# PhasedArrayReceiver.net
KiCad netlist of a schematic drawn in EAGLE
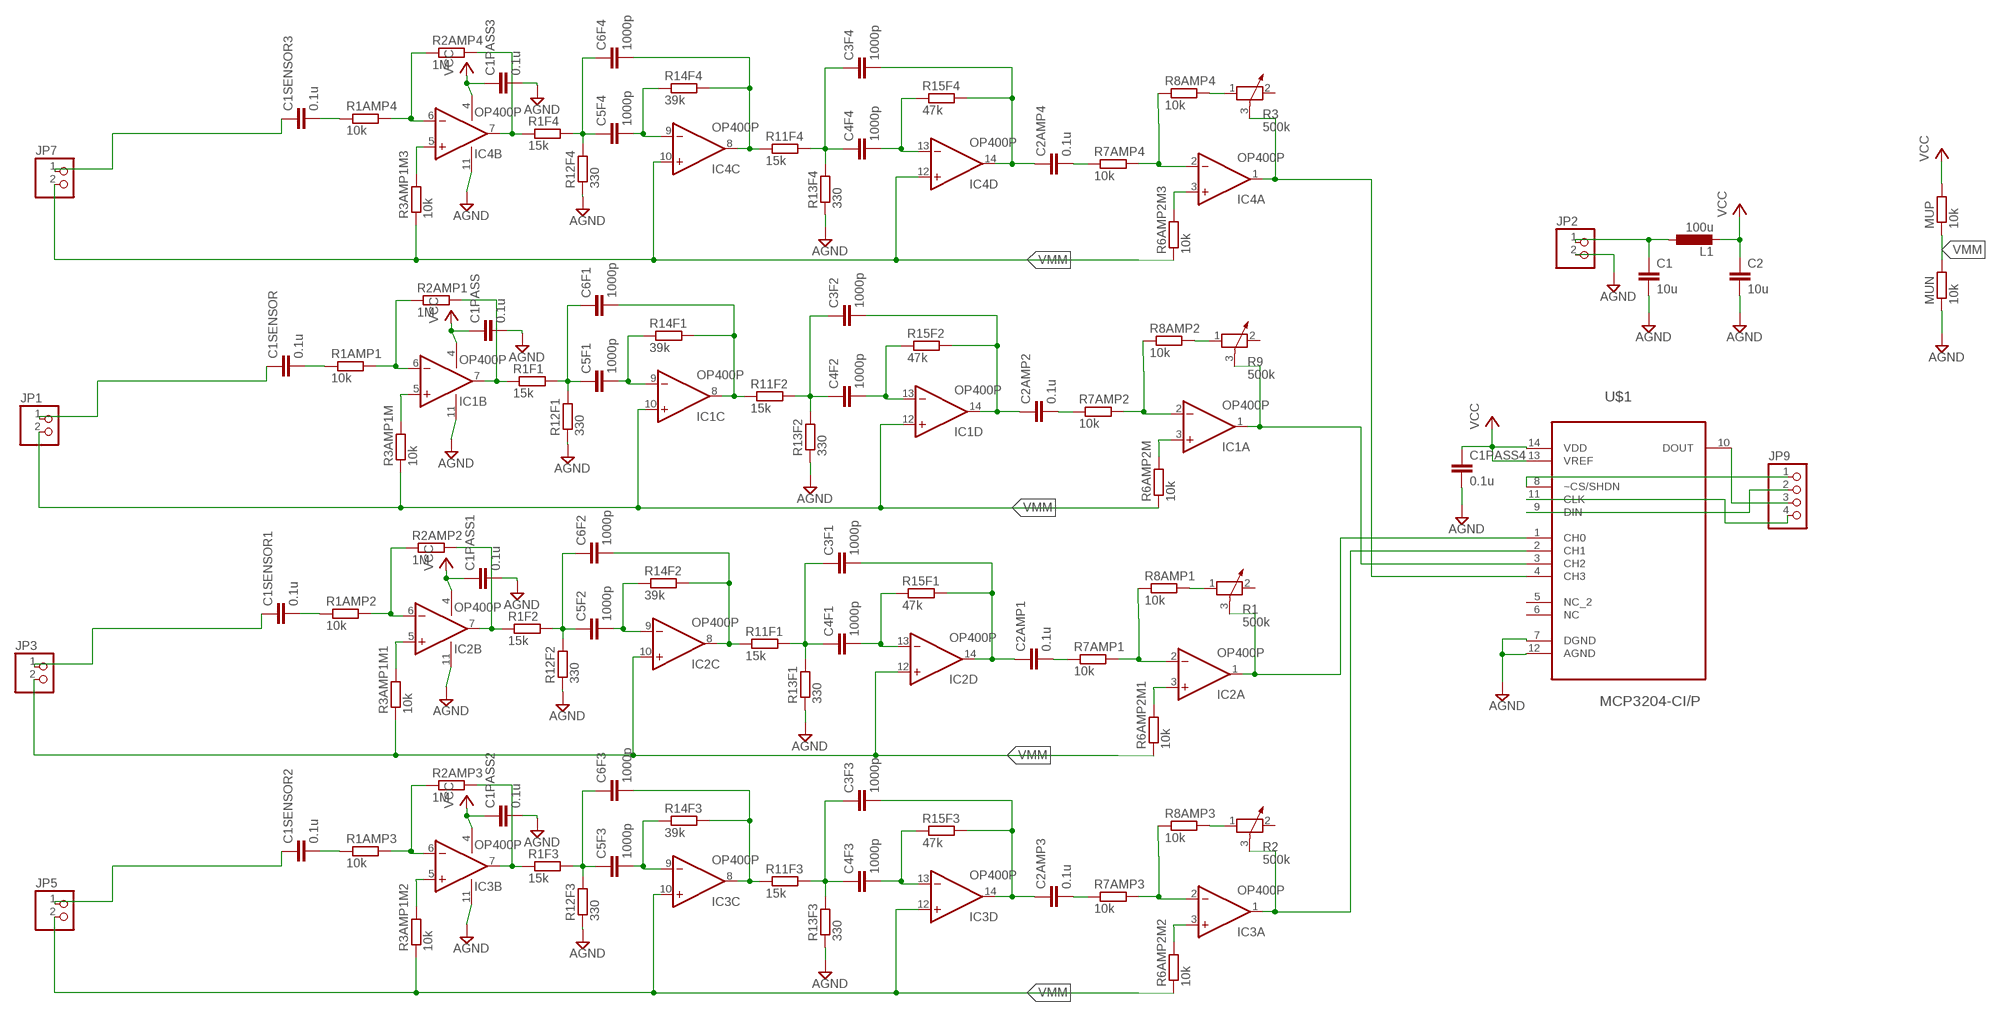
[diagram p0: schematic, sheet 1]

(export (version "E")
  (design (tool "Eeschema 10.0.6"))
  (components
    (comp (ref "C1")
      (value "10u")
      (footprint "eagle-import:C025-024X044")
      (libsource (lib "eagle-import") (part "C-EU025-024X044"))
    )
    (comp (ref "C1PASS")
      (value "0.1u")
      (footprint "eagle-import:C025-024X044")
      (libsource (lib "eagle-import") (part "C-EU025-024X044"))
    )
    (comp (ref "C1PASS1")
      (value "0.1u")
      (footprint "eagle-import:C025-024X044")
      (libsource (lib "eagle-import") (part "C-EU025-024X044"))
    )
    (comp (ref "C1PASS2")
      (value "0.1u")
      (footprint "eagle-import:C025-024X044")
      (libsource (lib "eagle-import") (part "C-EU025-024X044"))
    )
    (comp (ref "C1PASS3")
      (value "0.1u")
      (footprint "eagle-import:C025-024X044")
      (libsource (lib "eagle-import") (part "C-EU025-024X044"))
    )
    (comp (ref "C1PASS4")
      (value "0.1u")
      (footprint "eagle-import:C025-024X044")
      (libsource (lib "eagle-import") (part "C-EU025-024X044"))
    )
    (comp (ref "C1SENSOR")
      (value "0.1u")
      (footprint "eagle-import:C0603K")
      (libsource (lib "eagle-import") (part "C-EUC0603K"))
    )
    (comp (ref "C1SENSOR1")
      (value "0.1u")
      (footprint "eagle-import:C0603K")
      (libsource (lib "eagle-import") (part "C-EUC0603K"))
    )
    (comp (ref "C1SENSOR2")
      (value "0.1u")
      (footprint "eagle-import:C0603K")
      (libsource (lib "eagle-import") (part "C-EUC0603K"))
    )
    (comp (ref "C1SENSOR3")
      (value "0.1u")
      (footprint "eagle-import:C0603K")
      (libsource (lib "eagle-import") (part "C-EUC0603K"))
    )
    (comp (ref "C2")
      (value "10u")
      (footprint "eagle-import:C025-024X044")
      (libsource (lib "eagle-import") (part "C-EU025-024X044"))
    )
    (comp (ref "C2AMP1")
      (value "0.1u")
      (footprint "eagle-import:C0603K")
      (libsource (lib "eagle-import") (part "C-EUC0603K"))
    )
    (comp (ref "C2AMP2")
      (value "0.1u")
      (footprint "eagle-import:C0603K")
      (libsource (lib "eagle-import") (part "C-EUC0603K"))
    )
    (comp (ref "C2AMP3")
      (value "0.1u")
      (footprint "eagle-import:C0603K")
      (libsource (lib "eagle-import") (part "C-EUC0603K"))
    )
    (comp (ref "C2AMP4")
      (value "0.1u")
      (footprint "eagle-import:C0603K")
      (libsource (lib "eagle-import") (part "C-EUC0603K"))
    )
    (comp (ref "C3F1")
      (value "1000p")
      (footprint "eagle-import:C0603K")
      (libsource (lib "eagle-import") (part "C-EUC0603K"))
    )
    (comp (ref "C3F2")
      (value "1000p")
      (footprint "eagle-import:C0603K")
      (libsource (lib "eagle-import") (part "C-EUC0603K"))
    )
    (comp (ref "C3F3")
      (value "1000p")
      (footprint "eagle-import:C0603K")
      (libsource (lib "eagle-import") (part "C-EUC0603K"))
    )
    (comp (ref "C3F4")
      (value "1000p")
      (footprint "eagle-import:C0603K")
      (libsource (lib "eagle-import") (part "C-EUC0603K"))
    )
    (comp (ref "C4F1")
      (value "1000p")
      (footprint "eagle-import:C0603K")
      (libsource (lib "eagle-import") (part "C-EUC0603K"))
    )
    (comp (ref "C4F2")
      (value "1000p")
      (footprint "eagle-import:C0603K")
      (libsource (lib "eagle-import") (part "C-EUC0603K"))
    )
    (comp (ref "C4F3")
      (value "1000p")
      (footprint "eagle-import:C0603K")
      (libsource (lib "eagle-import") (part "C-EUC0603K"))
    )
    (comp (ref "C4F4")
      (value "1000p")
      (footprint "eagle-import:C0603K")
      (libsource (lib "eagle-import") (part "C-EUC0603K"))
    )
    (comp (ref "C5F1")
      (value "1000p")
      (footprint "eagle-import:C0603K")
      (libsource (lib "eagle-import") (part "C-EUC0603K"))
    )
    (comp (ref "C5F2")
      (value "1000p")
      (footprint "eagle-import:C0603K")
      (libsource (lib "eagle-import") (part "C-EUC0603K"))
    )
    (comp (ref "C5F3")
      (value "1000p")
      (footprint "eagle-import:C0603K")
      (libsource (lib "eagle-import") (part "C-EUC0603K"))
    )
    (comp (ref "C5F4")
      (value "1000p")
      (footprint "eagle-import:C0603K")
      (libsource (lib "eagle-import") (part "C-EUC0603K"))
    )
    (comp (ref "C6F1")
      (value "1000p")
      (footprint "eagle-import:C0603K")
      (libsource (lib "eagle-import") (part "C-EUC0603K"))
    )
    (comp (ref "C6F2")
      (value "1000p")
      (footprint "eagle-import:C0603K")
      (libsource (lib "eagle-import") (part "C-EUC0603K"))
    )
    (comp (ref "C6F3")
      (value "1000p")
      (footprint "eagle-import:C0603K")
      (libsource (lib "eagle-import") (part "C-EUC0603K"))
    )
    (comp (ref "C6F4")
      (value "1000p")
      (footprint "eagle-import:C0603K")
      (libsource (lib "eagle-import") (part "C-EUC0603K"))
    )
    (comp (ref "IC1")
      (value "OP400P")
      (footprint "eagle-import:DIL14")
      (libsource (lib "eagle-import") (part "OP400P"))
    )
    (comp (ref "IC2")
      (value "OP400P")
      (footprint "eagle-import:DIL14")
      (libsource (lib "eagle-import") (part "OP400P"))
    )
    (comp (ref "IC3")
      (value "OP400P")
      (footprint "eagle-import:DIL14")
      (libsource (lib "eagle-import") (part "OP400P"))
    )
    (comp (ref "IC4")
      (value "OP400P")
      (footprint "eagle-import:DIL14")
      (libsource (lib "eagle-import") (part "OP400P"))
    )
    (comp (ref "JP1")
      (value "PINHD-1X2")
      (footprint "eagle-import:1X02")
      (libsource (lib "eagle-import") (part "PINHD-1X2"))
    )
    (comp (ref "JP2")
      (value "PINHD-1X2")
      (footprint "eagle-import:1X02")
      (libsource (lib "eagle-import") (part "PINHD-1X2"))
    )
    (comp (ref "JP3")
      (value "PINHD-1X2")
      (footprint "eagle-import:1X02")
      (libsource (lib "eagle-import") (part "PINHD-1X2"))
    )
    (comp (ref "JP5")
      (value "PINHD-1X2")
      (footprint "eagle-import:1X02")
      (libsource (lib "eagle-import") (part "PINHD-1X2"))
    )
    (comp (ref "JP7")
      (value "PINHD-1X2")
      (footprint "eagle-import:1X02")
      (libsource (lib "eagle-import") (part "PINHD-1X2"))
    )
    (comp (ref "JP9")
      (value "PINHD-1X4")
      (footprint "eagle-import:1X04")
      (libsource (lib "eagle-import") (part "PINHD-1X4"))
    )
    (comp (ref "L1")
      (value "100u")
      (footprint "eagle-import:0207_7")
      (libsource (lib "eagle-import") (part "L-EU0207/7"))
    )
    (comp (ref "MUN")
      (value "10k")
      (footprint "eagle-import:0207_7")
      (libsource (lib "eagle-import") (part "R-EU_0207/7"))
    )
    (comp (ref "MUP")
      (value "10k")
      (footprint "eagle-import:0207_7")
      (libsource (lib "eagle-import") (part "R-EU_0207/7"))
    )
    (comp (ref "R1")
      (value "500k")
      (footprint "eagle-import:PT-10")
      (libsource (lib "eagle-import") (part "POTENTIOMETER_PT-10"))
    )
    (comp (ref "R1AMP1")
      (value "10k")
      (footprint "eagle-import:R0603")
      (libsource (lib "eagle-import") (part "R-EU_R0603"))
    )
    (comp (ref "R1AMP2")
      (value "10k")
      (footprint "eagle-import:R0603")
      (libsource (lib "eagle-import") (part "R-EU_R0603"))
    )
    (comp (ref "R1AMP3")
      (value "10k")
      (footprint "eagle-import:R0603")
      (libsource (lib "eagle-import") (part "R-EU_R0603"))
    )
    (comp (ref "R1AMP4")
      (value "10k")
      (footprint "eagle-import:R0603")
      (libsource (lib "eagle-import") (part "R-EU_R0603"))
    )
    (comp (ref "R1F1")
      (value "15k")
      (footprint "eagle-import:0207_7")
      (libsource (lib "eagle-import") (part "R-EU_0207/7"))
    )
    (comp (ref "R1F2")
      (value "15k")
      (footprint "eagle-import:0207_7")
      (libsource (lib "eagle-import") (part "R-EU_0207/7"))
    )
    (comp (ref "R1F3")
      (value "15k")
      (footprint "eagle-import:0207_7")
      (libsource (lib "eagle-import") (part "R-EU_0207/7"))
    )
    (comp (ref "R1F4")
      (value "15k")
      (footprint "eagle-import:0207_7")
      (libsource (lib "eagle-import") (part "R-EU_0207/7"))
    )
    (comp (ref "R2")
      (value "500k")
      (footprint "eagle-import:PT-10")
      (libsource (lib "eagle-import") (part "POTENTIOMETER_PT-10"))
    )
    (comp (ref "R2AMP1")
      (value "1M")
      (footprint "eagle-import:R0603")
      (libsource (lib "eagle-import") (part "R-EU_R0603"))
    )
    (comp (ref "R2AMP2")
      (value "1M")
      (footprint "eagle-import:R0603")
      (libsource (lib "eagle-import") (part "R-EU_R0603"))
    )
    (comp (ref "R2AMP3")
      (value "1M")
      (footprint "eagle-import:R0603")
      (libsource (lib "eagle-import") (part "R-EU_R0603"))
    )
    (comp (ref "R2AMP4")
      (value "1M")
      (footprint "eagle-import:R0603")
      (libsource (lib "eagle-import") (part "R-EU_R0603"))
    )
    (comp (ref "R3")
      (value "500k")
      (footprint "eagle-import:PT-10")
      (libsource (lib "eagle-import") (part "POTENTIOMETER_PT-10"))
    )
    (comp (ref "R3AMP1M")
      (value "10k")
      (footprint "eagle-import:R0603")
      (libsource (lib "eagle-import") (part "R-EU_R0603"))
    )
    (comp (ref "R3AMP1M1")
      (value "10k")
      (footprint "eagle-import:R0603")
      (libsource (lib "eagle-import") (part "R-EU_R0603"))
    )
    (comp (ref "R3AMP1M2")
      (value "10k")
      (footprint "eagle-import:R0603")
      (libsource (lib "eagle-import") (part "R-EU_R0603"))
    )
    (comp (ref "R3AMP1M3")
      (value "10k")
      (footprint "eagle-import:R0603")
      (libsource (lib "eagle-import") (part "R-EU_R0603"))
    )
    (comp (ref "R6AMP2M")
      (value "10k")
      (footprint "eagle-import:R0603")
      (libsource (lib "eagle-import") (part "R-EU_R0603"))
    )
    (comp (ref "R6AMP2M1")
      (value "10k")
      (footprint "eagle-import:R0603")
      (libsource (lib "eagle-import") (part "R-EU_R0603"))
    )
    (comp (ref "R6AMP2M2")
      (value "10k")
      (footprint "eagle-import:R0603")
      (libsource (lib "eagle-import") (part "R-EU_R0603"))
    )
    (comp (ref "R6AMP2M3")
      (value "10k")
      (footprint "eagle-import:R0603")
      (libsource (lib "eagle-import") (part "R-EU_R0603"))
    )
    (comp (ref "R7AMP1")
      (value "10k")
      (footprint "eagle-import:R0603")
      (libsource (lib "eagle-import") (part "R-EU_R0603"))
    )
    (comp (ref "R7AMP2")
      (value "10k")
      (footprint "eagle-import:R0603")
      (libsource (lib "eagle-import") (part "R-EU_R0603"))
    )
    (comp (ref "R7AMP3")
      (value "10k")
      (footprint "eagle-import:R0603")
      (libsource (lib "eagle-import") (part "R-EU_R0603"))
    )
    (comp (ref "R7AMP4")
      (value "10k")
      (footprint "eagle-import:R0603")
      (libsource (lib "eagle-import") (part "R-EU_R0603"))
    )
    (comp (ref "R8AMP1")
      (value "10k")
      (footprint "eagle-import:R0603")
      (libsource (lib "eagle-import") (part "R-EU_R0603"))
    )
    (comp (ref "R8AMP2")
      (value "10k")
      (footprint "eagle-import:R0603")
      (libsource (lib "eagle-import") (part "R-EU_R0603"))
    )
    (comp (ref "R8AMP3")
      (value "10k")
      (footprint "eagle-import:R0603")
      (libsource (lib "eagle-import") (part "R-EU_R0603"))
    )
    (comp (ref "R8AMP4")
      (value "10k")
      (footprint "eagle-import:R0603")
      (libsource (lib "eagle-import") (part "R-EU_R0603"))
    )
    (comp (ref "R9")
      (value "500k")
      (footprint "eagle-import:PT-10")
      (libsource (lib "eagle-import") (part "POTENTIOMETER_PT-10"))
    )
    (comp (ref "R11F1")
      (value "15k")
      (footprint "eagle-import:R0603")
      (libsource (lib "eagle-import") (part "R-EU_R0603"))
    )
    (comp (ref "R11F2")
      (value "15k")
      (footprint "eagle-import:R0603")
      (libsource (lib "eagle-import") (part "R-EU_R0603"))
    )
    (comp (ref "R11F3")
      (value "15k")
      (footprint "eagle-import:R0603")
      (libsource (lib "eagle-import") (part "R-EU_R0603"))
    )
    (comp (ref "R11F4")
      (value "15k")
      (footprint "eagle-import:R0603")
      (libsource (lib "eagle-import") (part "R-EU_R0603"))
    )
    (comp (ref "R12F1")
      (value "330")
      (footprint "eagle-import:R0603")
      (libsource (lib "eagle-import") (part "R-EU_R0603"))
    )
    (comp (ref "R12F2")
      (value "330")
      (footprint "eagle-import:R0603")
      (libsource (lib "eagle-import") (part "R-EU_R0603"))
    )
    (comp (ref "R12F3")
      (value "330")
      (footprint "eagle-import:R0603")
      (libsource (lib "eagle-import") (part "R-EU_R0603"))
    )
    (comp (ref "R12F4")
      (value "330")
      (footprint "eagle-import:R0603")
      (libsource (lib "eagle-import") (part "R-EU_R0603"))
    )
    (comp (ref "R13F1")
      (value "330")
      (footprint "eagle-import:R0603")
      (libsource (lib "eagle-import") (part "R-EU_R0603"))
    )
    (comp (ref "R13F2")
      (value "330")
      (footprint "eagle-import:R0603")
      (libsource (lib "eagle-import") (part "R-EU_R0603"))
    )
    (comp (ref "R13F3")
      (value "330")
      (footprint "eagle-import:R0603")
      (libsource (lib "eagle-import") (part "R-EU_R0603"))
    )
    (comp (ref "R13F4")
      (value "330")
      (footprint "eagle-import:R0603")
      (libsource (lib "eagle-import") (part "R-EU_R0603"))
    )
    (comp (ref "R14F1")
      (value "39k")
      (footprint "eagle-import:0207_7")
      (libsource (lib "eagle-import") (part "R-EU_0207/7"))
    )
    (comp (ref "R14F2")
      (value "39k")
      (footprint "eagle-import:0207_7")
      (libsource (lib "eagle-import") (part "R-EU_0207/7"))
    )
    (comp (ref "R14F3")
      (value "39k")
      (footprint "eagle-import:0207_7")
      (libsource (lib "eagle-import") (part "R-EU_0207/7"))
    )
    (comp (ref "R14F4")
      (value "39k")
      (footprint "eagle-import:0207_7")
      (libsource (lib "eagle-import") (part "R-EU_0207/7"))
    )
    (comp (ref "R15F1")
      (value "47k")
      (footprint "eagle-import:0207_7")
      (libsource (lib "eagle-import") (part "R-EU_0207/7"))
    )
    (comp (ref "R15F2")
      (value "47k")
      (footprint "eagle-import:0207_7")
      (libsource (lib "eagle-import") (part "R-EU_0207/7"))
    )
    (comp (ref "R15F3")
      (value "47k")
      (footprint "eagle-import:0207_7")
      (libsource (lib "eagle-import") (part "R-EU_0207/7"))
    )
    (comp (ref "R15F4")
      (value "47k")
      (footprint "eagle-import:0207_7")
      (libsource (lib "eagle-import") (part "R-EU_0207/7"))
    )
    (comp (ref "U$1")
      (value "MCP3204-CI/P")
      (footprint "eagle-import:DIP254P762X432-14")
      (fields (field (name "MF") "Microchip"))
      (libsource (lib "eagle-import") (part "MCP3204-CI/P"))
    )
  )
  (nets
    (net (code "1") (name "AGND") (class "Default")
      (node (ref "C1") (pin "2") (pinfunction "2_2") (pintype "passive"))
      (node (ref "C1PASS") (pin "2") (pinfunction "2_2") (pintype "passive"))
      (node (ref "C1PASS1") (pin "2") (pinfunction "2_2") (pintype "passive"))
      (node (ref "C1PASS2") (pin "2") (pinfunction "2_2") (pintype "passive"))
      (node (ref "C1PASS3") (pin "2") (pinfunction "2_2") (pintype "passive"))
      (node (ref "C1PASS4") (pin "2") (pinfunction "2_2") (pintype "passive"))
      (node (ref "C2") (pin "2") (pinfunction "2_2") (pintype "passive"))
      (node (ref "IC1") (pin "11") (pinfunction "V-_11") (pintype "power_in"))
      (node (ref "IC2") (pin "11") (pinfunction "V-_11") (pintype "power_in"))
      (node (ref "IC3") (pin "11") (pinfunction "V-_11") (pintype "power_in"))
      (node (ref "IC4") (pin "11") (pinfunction "V-_11") (pintype "power_in"))
      (node (ref "JP2") (pin "2") (pinfunction "2_2") (pintype "passive"))
      (node (ref "MUN") (pin "1") (pinfunction "1_1") (pintype "passive"))
      (node (ref "R12F1") (pin "1") (pinfunction "1_1") (pintype "passive"))
      (node (ref "R12F2") (pin "1") (pinfunction "1_1") (pintype "passive"))
      (node (ref "R12F3") (pin "1") (pinfunction "1_1") (pintype "passive"))
      (node (ref "R12F4") (pin "1") (pinfunction "1_1") (pintype "passive"))
      (node (ref "R13F1") (pin "1") (pinfunction "1_1") (pintype "passive"))
      (node (ref "R13F2") (pin "1") (pinfunction "1_1") (pintype "passive"))
      (node (ref "R13F3") (pin "1") (pinfunction "1_1") (pintype "passive"))
      (node (ref "R13F4") (pin "1") (pinfunction "1_1") (pintype "passive"))
      (node (ref "U$1") (pin "12") (pinfunction "AGND_12") (pintype "passive"))
      (node (ref "U$1") (pin "7") (pinfunction "DGND_7") (pintype "passive"))
    )
    (net (code "2") (name "Net-(C1-Pad1)") (class "Default")
      (node (ref "C1") (pin "1") (pinfunction "1_1") (pintype "passive"))
      (node (ref "JP2") (pin "1") (pinfunction "1_1") (pintype "passive"))
      (node (ref "L1") (pin "1") (pinfunction "1_1") (pintype "passive"))
    )
    (net (code "3") (name "Net-(C1SENSOR-Pad1)") (class "Default")
      (node (ref "C1SENSOR") (pin "1") (pinfunction "1_1") (pintype "passive"))
      (node (ref "JP1") (pin "1") (pinfunction "1_1") (pintype "passive"))
    )
    (net (code "4") (name "Net-(C1SENSOR-Pad2)") (class "Default")
      (node (ref "C1SENSOR") (pin "2") (pinfunction "2_2") (pintype "passive"))
      (node (ref "R1AMP1") (pin "1") (pinfunction "1_1") (pintype "passive"))
    )
    (net (code "5") (name "Net-(C1SENSOR1-Pad1)") (class "Default")
      (node (ref "C1SENSOR1") (pin "1") (pinfunction "1_1") (pintype "passive"))
      (node (ref "JP3") (pin "1") (pinfunction "1_1") (pintype "passive"))
    )
    (net (code "6") (name "Net-(C1SENSOR1-Pad2)") (class "Default")
      (node (ref "C1SENSOR1") (pin "2") (pinfunction "2_2") (pintype "passive"))
      (node (ref "R1AMP2") (pin "1") (pinfunction "1_1") (pintype "passive"))
    )
    (net (code "7") (name "Net-(C1SENSOR2-Pad1)") (class "Default")
      (node (ref "C1SENSOR2") (pin "1") (pinfunction "1_1") (pintype "passive"))
      (node (ref "JP5") (pin "1") (pinfunction "1_1") (pintype "passive"))
    )
    (net (code "8") (name "Net-(C1SENSOR2-Pad2)") (class "Default")
      (node (ref "C1SENSOR2") (pin "2") (pinfunction "2_2") (pintype "passive"))
      (node (ref "R1AMP3") (pin "1") (pinfunction "1_1") (pintype "passive"))
    )
    (net (code "9") (name "Net-(C1SENSOR3-Pad1)") (class "Default")
      (node (ref "C1SENSOR3") (pin "1") (pinfunction "1_1") (pintype "passive"))
      (node (ref "JP7") (pin "1") (pinfunction "1_1") (pintype "passive"))
    )
    (net (code "10") (name "Net-(C1SENSOR3-Pad2)") (class "Default")
      (node (ref "C1SENSOR3") (pin "2") (pinfunction "2_2") (pintype "passive"))
      (node (ref "R1AMP4") (pin "1") (pinfunction "1_1") (pintype "passive"))
    )
    (net (code "11") (name "Net-(C2AMP1-Pad2)") (class "Default")
      (node (ref "C2AMP1") (pin "2") (pinfunction "2_2") (pintype "passive"))
      (node (ref "R7AMP1") (pin "1") (pinfunction "1_1") (pintype "passive"))
    )
    (net (code "12") (name "Net-(C2AMP2-Pad2)") (class "Default")
      (node (ref "C2AMP2") (pin "2") (pinfunction "2_2") (pintype "passive"))
      (node (ref "R7AMP2") (pin "1") (pinfunction "1_1") (pintype "passive"))
    )
    (net (code "13") (name "Net-(C2AMP3-Pad2)") (class "Default")
      (node (ref "C2AMP3") (pin "2") (pinfunction "2_2") (pintype "passive"))
      (node (ref "R7AMP3") (pin "1") (pinfunction "1_1") (pintype "passive"))
    )
    (net (code "14") (name "Net-(C2AMP4-Pad2)") (class "Default")
      (node (ref "C2AMP4") (pin "2") (pinfunction "2_2") (pintype "passive"))
      (node (ref "R7AMP4") (pin "1") (pinfunction "1_1") (pintype "passive"))
    )
    (net (code "15") (name "Net-(C3F1-Pad1)") (class "Default")
      (node (ref "C3F1") (pin "1") (pinfunction "1_1") (pintype "passive"))
      (node (ref "C4F1") (pin "1") (pinfunction "1_1") (pintype "passive"))
      (node (ref "R11F1") (pin "2") (pinfunction "2_2") (pintype "passive"))
      (node (ref "R13F1") (pin "2") (pinfunction "2_2") (pintype "passive"))
    )
    (net (code "16") (name "Net-(C3F2-Pad1)") (class "Default")
      (node (ref "C3F2") (pin "1") (pinfunction "1_1") (pintype "passive"))
      (node (ref "C4F2") (pin "1") (pinfunction "1_1") (pintype "passive"))
      (node (ref "R11F2") (pin "2") (pinfunction "2_2") (pintype "passive"))
      (node (ref "R13F2") (pin "2") (pinfunction "2_2") (pintype "passive"))
    )
    (net (code "17") (name "Net-(C3F3-Pad1)") (class "Default")
      (node (ref "C3F3") (pin "1") (pinfunction "1_1") (pintype "passive"))
      (node (ref "C4F3") (pin "1") (pinfunction "1_1") (pintype "passive"))
      (node (ref "R11F3") (pin "2") (pinfunction "2_2") (pintype "passive"))
      (node (ref "R13F3") (pin "2") (pinfunction "2_2") (pintype "passive"))
    )
    (net (code "18") (name "Net-(C3F4-Pad1)") (class "Default")
      (node (ref "C3F4") (pin "1") (pinfunction "1_1") (pintype "passive"))
      (node (ref "C4F4") (pin "1") (pinfunction "1_1") (pintype "passive"))
      (node (ref "R11F4") (pin "2") (pinfunction "2_2") (pintype "passive"))
      (node (ref "R13F4") (pin "2") (pinfunction "2_2") (pintype "passive"))
    )
    (net (code "19") (name "Net-(C5F1-Pad1)") (class "Default")
      (node (ref "C5F1") (pin "1") (pinfunction "1_1") (pintype "passive"))
      (node (ref "C6F1") (pin "1") (pinfunction "1_1") (pintype "passive"))
      (node (ref "R12F1") (pin "2") (pinfunction "2_2") (pintype "passive"))
      (node (ref "R1F1") (pin "2") (pinfunction "2_2") (pintype "passive"))
    )
    (net (code "20") (name "Net-(C5F2-Pad1)") (class "Default")
      (node (ref "C5F2") (pin "1") (pinfunction "1_1") (pintype "passive"))
      (node (ref "C6F2") (pin "1") (pinfunction "1_1") (pintype "passive"))
      (node (ref "R12F2") (pin "2") (pinfunction "2_2") (pintype "passive"))
      (node (ref "R1F2") (pin "2") (pinfunction "2_2") (pintype "passive"))
    )
    (net (code "21") (name "Net-(C5F3-Pad1)") (class "Default")
      (node (ref "C5F3") (pin "1") (pinfunction "1_1") (pintype "passive"))
      (node (ref "C6F3") (pin "1") (pinfunction "1_1") (pintype "passive"))
      (node (ref "R12F3") (pin "2") (pinfunction "2_2") (pintype "passive"))
      (node (ref "R1F3") (pin "2") (pinfunction "2_2") (pintype "passive"))
    )
    (net (code "22") (name "Net-(C5F4-Pad1)") (class "Default")
      (node (ref "C5F4") (pin "1") (pinfunction "1_1") (pintype "passive"))
      (node (ref "C6F4") (pin "1") (pinfunction "1_1") (pintype "passive"))
      (node (ref "R12F4") (pin "2") (pinfunction "2_2") (pintype "passive"))
      (node (ref "R1F4") (pin "2") (pinfunction "2_2") (pintype "passive"))
    )
    (net (code "23") (name "Net-(IC1A-+IN)") (class "Default")
      (node (ref "IC1") (pin "3") (pinfunction "+IN_3") (pintype "input"))
      (node (ref "R6AMP2M") (pin "2") (pinfunction "2_2") (pintype "passive"))
    )
    (net (code "24") (name "Net-(IC1A--IN)") (class "Default")
      (node (ref "IC1") (pin "2") (pinfunction "-IN_2") (pintype "input"))
      (node (ref "R7AMP2") (pin "2") (pinfunction "2_2") (pintype "passive"))
      (node (ref "R8AMP2") (pin "1") (pinfunction "1_1") (pintype "passive"))
    )
    (net (code "25") (name "Net-(IC1A-OUT)") (class "Default")
      (node (ref "IC1") (pin "1") (pinfunction "OUT_1") (pintype "output"))
      (node (ref "R9") (pin "3") (pinfunction "3_3") (pintype "passive"))
      (node (ref "U$1") (pin "3") (pinfunction "CH2_3") (pintype "input"))
    )
    (net (code "26") (name "Net-(IC1B-+IN)") (class "Default")
      (node (ref "IC1") (pin "5") (pinfunction "+IN_5") (pintype "input"))
      (node (ref "R3AMP1M") (pin "2") (pinfunction "2_2") (pintype "passive"))
    )
    (net (code "27") (name "Net-(IC1B--IN)") (class "Default")
      (node (ref "IC1") (pin "6") (pinfunction "-IN_6") (pintype "input"))
      (node (ref "R1AMP1") (pin "2") (pinfunction "2_2") (pintype "passive"))
      (node (ref "R2AMP1") (pin "1") (pinfunction "1_1") (pintype "passive"))
    )
    (net (code "28") (name "Net-(IC1B-OUT)") (class "Default")
      (node (ref "IC1") (pin "7") (pinfunction "OUT_7") (pintype "output"))
      (node (ref "R1F1") (pin "1") (pinfunction "1_1") (pintype "passive"))
      (node (ref "R2AMP1") (pin "2") (pinfunction "2_2") (pintype "passive"))
    )
    (net (code "29") (name "Net-(IC1C--IN)") (class "Default")
      (node (ref "C5F1") (pin "2") (pinfunction "2_2") (pintype "passive"))
      (node (ref "IC1") (pin "9") (pinfunction "-IN_9") (pintype "input"))
      (node (ref "R14F1") (pin "1") (pinfunction "1_1") (pintype "passive"))
    )
    (net (code "30") (name "Net-(IC1C-OUT)") (class "Default")
      (node (ref "C6F1") (pin "2") (pinfunction "2_2") (pintype "passive"))
      (node (ref "IC1") (pin "8") (pinfunction "OUT_8") (pintype "output"))
      (node (ref "R11F2") (pin "1") (pinfunction "1_1") (pintype "passive"))
      (node (ref "R14F1") (pin "2") (pinfunction "2_2") (pintype "passive"))
    )
    (net (code "31") (name "Net-(IC1D--IN)") (class "Default")
      (node (ref "C4F2") (pin "2") (pinfunction "2_2") (pintype "passive"))
      (node (ref "IC1") (pin "13") (pinfunction "-IN_13") (pintype "input"))
      (node (ref "R15F2") (pin "1") (pinfunction "1_1") (pintype "passive"))
    )
    (net (code "32") (name "Net-(IC1D-OUT)") (class "Default")
      (node (ref "C2AMP2") (pin "1") (pinfunction "1_1") (pintype "passive"))
      (node (ref "C3F2") (pin "2") (pinfunction "2_2") (pintype "passive"))
      (node (ref "IC1") (pin "14") (pinfunction "OUT_14") (pintype "output"))
      (node (ref "R15F2") (pin "2") (pinfunction "2_2") (pintype "passive"))
    )
    (net (code "33") (name "Net-(IC2A-+IN)") (class "Default")
      (node (ref "IC2") (pin "3") (pinfunction "+IN_3") (pintype "input"))
      (node (ref "R6AMP2M1") (pin "2") (pinfunction "2_2") (pintype "passive"))
    )
    (net (code "34") (name "Net-(IC2A--IN)") (class "Default")
      (node (ref "IC2") (pin "2") (pinfunction "-IN_2") (pintype "input"))
      (node (ref "R7AMP1") (pin "2") (pinfunction "2_2") (pintype "passive"))
      (node (ref "R8AMP1") (pin "1") (pinfunction "1_1") (pintype "passive"))
    )
    (net (code "35") (name "Net-(IC2A-OUT)") (class "Default")
      (node (ref "IC2") (pin "1") (pinfunction "OUT_1") (pintype "output"))
      (node (ref "R1") (pin "3") (pinfunction "3_3") (pintype "passive"))
      (node (ref "U$1") (pin "1") (pinfunction "CH0_1") (pintype "input"))
    )
    (net (code "36") (name "Net-(IC2B-+IN)") (class "Default")
      (node (ref "IC2") (pin "5") (pinfunction "+IN_5") (pintype "input"))
      (node (ref "R3AMP1M1") (pin "2") (pinfunction "2_2") (pintype "passive"))
    )
    (net (code "37") (name "Net-(IC2B--IN)") (class "Default")
      (node (ref "IC2") (pin "6") (pinfunction "-IN_6") (pintype "input"))
      (node (ref "R1AMP2") (pin "2") (pinfunction "2_2") (pintype "passive"))
      (node (ref "R2AMP2") (pin "1") (pinfunction "1_1") (pintype "passive"))
    )
    (net (code "38") (name "Net-(IC2B-OUT)") (class "Default")
      (node (ref "IC2") (pin "7") (pinfunction "OUT_7") (pintype "output"))
      (node (ref "R1F2") (pin "1") (pinfunction "1_1") (pintype "passive"))
      (node (ref "R2AMP2") (pin "2") (pinfunction "2_2") (pintype "passive"))
    )
    (net (code "39") (name "Net-(IC2C--IN)") (class "Default")
      (node (ref "C5F2") (pin "2") (pinfunction "2_2") (pintype "passive"))
      (node (ref "IC2") (pin "9") (pinfunction "-IN_9") (pintype "input"))
      (node (ref "R14F2") (pin "1") (pinfunction "1_1") (pintype "passive"))
    )
    (net (code "40") (name "Net-(IC2C-OUT)") (class "Default")
      (node (ref "C6F2") (pin "2") (pinfunction "2_2") (pintype "passive"))
      (node (ref "IC2") (pin "8") (pinfunction "OUT_8") (pintype "output"))
      (node (ref "R11F1") (pin "1") (pinfunction "1_1") (pintype "passive"))
      (node (ref "R14F2") (pin "2") (pinfunction "2_2") (pintype "passive"))
    )
    (net (code "41") (name "Net-(IC2D--IN)") (class "Default")
      (node (ref "C4F1") (pin "2") (pinfunction "2_2") (pintype "passive"))
      (node (ref "IC2") (pin "13") (pinfunction "-IN_13") (pintype "input"))
      (node (ref "R15F1") (pin "1") (pinfunction "1_1") (pintype "passive"))
    )
    (net (code "42") (name "Net-(IC2D-OUT)") (class "Default")
      (node (ref "C2AMP1") (pin "1") (pinfunction "1_1") (pintype "passive"))
      (node (ref "C3F1") (pin "2") (pinfunction "2_2") (pintype "passive"))
      (node (ref "IC2") (pin "14") (pinfunction "OUT_14") (pintype "output"))
      (node (ref "R15F1") (pin "2") (pinfunction "2_2") (pintype "passive"))
    )
    (net (code "43") (name "Net-(IC3A-+IN)") (class "Default")
      (node (ref "IC3") (pin "3") (pinfunction "+IN_3") (pintype "input"))
      (node (ref "R6AMP2M2") (pin "2") (pinfunction "2_2") (pintype "passive"))
    )
    (net (code "44") (name "Net-(IC3A--IN)") (class "Default")
      (node (ref "IC3") (pin "2") (pinfunction "-IN_2") (pintype "input"))
      (node (ref "R7AMP3") (pin "2") (pinfunction "2_2") (pintype "passive"))
      (node (ref "R8AMP3") (pin "1") (pinfunction "1_1") (pintype "passive"))
    )
    (net (code "45") (name "Net-(IC3A-OUT)") (class "Default")
      (node (ref "IC3") (pin "1") (pinfunction "OUT_1") (pintype "output"))
      (node (ref "R2") (pin "3") (pinfunction "3_3") (pintype "passive"))
      (node (ref "U$1") (pin "2") (pinfunction "CH1_2") (pintype "input"))
    )
    (net (code "46") (name "Net-(IC3B-+IN)") (class "Default")
      (node (ref "IC3") (pin "5") (pinfunction "+IN_5") (pintype "input"))
      (node (ref "R3AMP1M2") (pin "2") (pinfunction "2_2") (pintype "passive"))
    )
    (net (code "47") (name "Net-(IC3B--IN)") (class "Default")
      (node (ref "IC3") (pin "6") (pinfunction "-IN_6") (pintype "input"))
      (node (ref "R1AMP3") (pin "2") (pinfunction "2_2") (pintype "passive"))
      (node (ref "R2AMP3") (pin "1") (pinfunction "1_1") (pintype "passive"))
    )
    (net (code "48") (name "Net-(IC3B-OUT)") (class "Default")
      (node (ref "IC3") (pin "7") (pinfunction "OUT_7") (pintype "output"))
      (node (ref "R1F3") (pin "1") (pinfunction "1_1") (pintype "passive"))
      (node (ref "R2AMP3") (pin "2") (pinfunction "2_2") (pintype "passive"))
    )
    (net (code "49") (name "Net-(IC3C--IN)") (class "Default")
      (node (ref "C5F3") (pin "2") (pinfunction "2_2") (pintype "passive"))
      (node (ref "IC3") (pin "9") (pinfunction "-IN_9") (pintype "input"))
      (node (ref "R14F3") (pin "1") (pinfunction "1_1") (pintype "passive"))
    )
    (net (code "50") (name "Net-(IC3C-OUT)") (class "Default")
      (node (ref "C6F3") (pin "2") (pinfunction "2_2") (pintype "passive"))
      (node (ref "IC3") (pin "8") (pinfunction "OUT_8") (pintype "output"))
      (node (ref "R11F3") (pin "1") (pinfunction "1_1") (pintype "passive"))
      (node (ref "R14F3") (pin "2") (pinfunction "2_2") (pintype "passive"))
    )
    (net (code "51") (name "Net-(IC3D--IN)") (class "Default")
      (node (ref "C4F3") (pin "2") (pinfunction "2_2") (pintype "passive"))
      (node (ref "IC3") (pin "13") (pinfunction "-IN_13") (pintype "input"))
      (node (ref "R15F3") (pin "1") (pinfunction "1_1") (pintype "passive"))
    )
    (net (code "52") (name "Net-(IC3D-OUT)") (class "Default")
      (node (ref "C2AMP3") (pin "1") (pinfunction "1_1") (pintype "passive"))
      (node (ref "C3F3") (pin "2") (pinfunction "2_2") (pintype "passive"))
      (node (ref "IC3") (pin "14") (pinfunction "OUT_14") (pintype "output"))
      (node (ref "R15F3") (pin "2") (pinfunction "2_2") (pintype "passive"))
    )
    (net (code "53") (name "Net-(IC4A-+IN)") (class "Default")
      (node (ref "IC4") (pin "3") (pinfunction "+IN_3") (pintype "input"))
      (node (ref "R6AMP2M3") (pin "2") (pinfunction "2_2") (pintype "passive"))
    )
    (net (code "54") (name "Net-(IC4A--IN)") (class "Default")
      (node (ref "IC4") (pin "2") (pinfunction "-IN_2") (pintype "input"))
      (node (ref "R7AMP4") (pin "2") (pinfunction "2_2") (pintype "passive"))
      (node (ref "R8AMP4") (pin "1") (pinfunction "1_1") (pintype "passive"))
    )
    (net (code "55") (name "Net-(IC4A-OUT)") (class "Default")
      (node (ref "IC4") (pin "1") (pinfunction "OUT_1") (pintype "output"))
      (node (ref "R3") (pin "3") (pinfunction "3_3") (pintype "passive"))
      (node (ref "U$1") (pin "4") (pinfunction "CH3_4") (pintype "input"))
    )
    (net (code "56") (name "Net-(IC4B-+IN)") (class "Default")
      (node (ref "IC4") (pin "5") (pinfunction "+IN_5") (pintype "input"))
      (node (ref "R3AMP1M3") (pin "2") (pinfunction "2_2") (pintype "passive"))
    )
    (net (code "57") (name "Net-(IC4B--IN)") (class "Default")
      (node (ref "IC4") (pin "6") (pinfunction "-IN_6") (pintype "input"))
      (node (ref "R1AMP4") (pin "2") (pinfunction "2_2") (pintype "passive"))
      (node (ref "R2AMP4") (pin "1") (pinfunction "1_1") (pintype "passive"))
    )
    (net (code "58") (name "Net-(IC4B-OUT)") (class "Default")
      (node (ref "IC4") (pin "7") (pinfunction "OUT_7") (pintype "output"))
      (node (ref "R1F4") (pin "1") (pinfunction "1_1") (pintype "passive"))
      (node (ref "R2AMP4") (pin "2") (pinfunction "2_2") (pintype "passive"))
    )
    (net (code "59") (name "Net-(IC4C--IN)") (class "Default")
      (node (ref "C5F4") (pin "2") (pinfunction "2_2") (pintype "passive"))
      (node (ref "IC4") (pin "9") (pinfunction "-IN_9") (pintype "input"))
      (node (ref "R14F4") (pin "1") (pinfunction "1_1") (pintype "passive"))
    )
    (net (code "60") (name "Net-(IC4C-OUT)") (class "Default")
      (node (ref "C6F4") (pin "2") (pinfunction "2_2") (pintype "passive"))
      (node (ref "IC4") (pin "8") (pinfunction "OUT_8") (pintype "output"))
      (node (ref "R11F4") (pin "1") (pinfunction "1_1") (pintype "passive"))
      (node (ref "R14F4") (pin "2") (pinfunction "2_2") (pintype "passive"))
    )
    (net (code "61") (name "Net-(IC4D--IN)") (class "Default")
      (node (ref "C4F4") (pin "2") (pinfunction "2_2") (pintype "passive"))
      (node (ref "IC4") (pin "13") (pinfunction "-IN_13") (pintype "input"))
      (node (ref "R15F4") (pin "1") (pinfunction "1_1") (pintype "passive"))
    )
    (net (code "62") (name "Net-(IC4D-OUT)") (class "Default")
      (node (ref "C2AMP4") (pin "1") (pinfunction "1_1") (pintype "passive"))
      (node (ref "C3F4") (pin "2") (pinfunction "2_2") (pintype "passive"))
      (node (ref "IC4") (pin "14") (pinfunction "OUT_14") (pintype "output"))
      (node (ref "R15F4") (pin "2") (pinfunction "2_2") (pintype "passive"))
    )
    (net (code "63") (name "Net-(R1-Pad1)") (class "Default")
      (node (ref "R1") (pin "1") (pinfunction "1_1") (pintype "passive"))
      (node (ref "R8AMP1") (pin "2") (pinfunction "2_2") (pintype "passive"))
    )
    (net (code "64") (name "Net-(R2-Pad1)") (class "Default")
      (node (ref "R2") (pin "1") (pinfunction "1_1") (pintype "passive"))
      (node (ref "R8AMP3") (pin "2") (pinfunction "2_2") (pintype "passive"))
    )
    (net (code "65") (name "Net-(R3-Pad1)") (class "Default")
      (node (ref "R3") (pin "1") (pinfunction "1_1") (pintype "passive"))
      (node (ref "R8AMP4") (pin "2") (pinfunction "2_2") (pintype "passive"))
    )
    (net (code "66") (name "Net-(R8AMP2-Pad2)") (class "Default")
      (node (ref "R8AMP2") (pin "2") (pinfunction "2_2") (pintype "passive"))
      (node (ref "R9") (pin "1") (pinfunction "1_1") (pintype "passive"))
    )
    (net (code "67") (name "Net-(U$1-CLK)") (class "Default")
      (node (ref "JP9") (pin "4") (pinfunction "4_4") (pintype "passive"))
      (node (ref "U$1") (pin "11") (pinfunction "CLK_11") (pintype "input"))
    )
    (net (code "68") (name "Net-(U$1-DIN)") (class "Default")
      (node (ref "JP9") (pin "2") (pinfunction "2_2") (pintype "passive"))
      (node (ref "U$1") (pin "9") (pinfunction "DIN_9") (pintype "input"))
    )
    (net (code "69") (name "Net-(U$1-DOUT)") (class "Default")
      (node (ref "JP9") (pin "3") (pinfunction "3_3") (pintype "passive"))
      (node (ref "U$1") (pin "10") (pinfunction "DOUT_10") (pintype "output"))
    )
    (net (code "70") (name "Net-(U$1-~{CS{slash}SHDN})") (class "Default")
      (node (ref "JP9") (pin "1") (pinfunction "1_1") (pintype "passive"))
      (node (ref "U$1") (pin "8") (pinfunction "~{CS/SHDN}_8") (pintype "input"))
    )
    (net (code "71") (name "VCC") (class "Default")
      (node (ref "C1PASS") (pin "1") (pinfunction "1_1") (pintype "passive"))
      (node (ref "C1PASS1") (pin "1") (pinfunction "1_1") (pintype "passive"))
      (node (ref "C1PASS2") (pin "1") (pinfunction "1_1") (pintype "passive"))
      (node (ref "C1PASS3") (pin "1") (pinfunction "1_1") (pintype "passive"))
      (node (ref "C1PASS4") (pin "1") (pinfunction "1_1") (pintype "passive"))
      (node (ref "C2") (pin "1") (pinfunction "1_1") (pintype "passive"))
      (node (ref "IC1") (pin "4") (pinfunction "V+_4") (pintype "power_in"))
      (node (ref "IC2") (pin "4") (pinfunction "V+_4") (pintype "power_in"))
      (node (ref "IC3") (pin "4") (pinfunction "V+_4") (pintype "power_in"))
      (node (ref "IC4") (pin "4") (pinfunction "V+_4") (pintype "power_in"))
      (node (ref "L1") (pin "2") (pinfunction "2_2") (pintype "passive"))
      (node (ref "MUP") (pin "2") (pinfunction "2_2") (pintype "passive"))
      (node (ref "U$1") (pin "13") (pinfunction "VREF_13") (pintype "power_in"))
      (node (ref "U$1") (pin "14") (pinfunction "VDD_14") (pintype "power_in"))
    )
    (net (code "72") (name "VMM") (class "Default")
      (node (ref "IC1") (pin "10") (pinfunction "+IN_10") (pintype "input"))
      (node (ref "IC1") (pin "12") (pinfunction "+IN_12") (pintype "input"))
      (node (ref "IC2") (pin "10") (pinfunction "+IN_10") (pintype "input"))
      (node (ref "IC2") (pin "12") (pinfunction "+IN_12") (pintype "input"))
      (node (ref "IC3") (pin "10") (pinfunction "+IN_10") (pintype "input"))
      (node (ref "IC3") (pin "12") (pinfunction "+IN_12") (pintype "input"))
      (node (ref "IC4") (pin "10") (pinfunction "+IN_10") (pintype "input"))
      (node (ref "IC4") (pin "12") (pinfunction "+IN_12") (pintype "input"))
      (node (ref "JP1") (pin "2") (pinfunction "2_2") (pintype "passive"))
      (node (ref "JP3") (pin "2") (pinfunction "2_2") (pintype "passive"))
      (node (ref "JP5") (pin "2") (pinfunction "2_2") (pintype "passive"))
      (node (ref "JP7") (pin "2") (pinfunction "2_2") (pintype "passive"))
      (node (ref "MUN") (pin "2") (pinfunction "2_2") (pintype "passive"))
      (node (ref "MUP") (pin "1") (pinfunction "1_1") (pintype "passive"))
      (node (ref "R3AMP1M") (pin "1") (pinfunction "1_1") (pintype "passive"))
      (node (ref "R3AMP1M1") (pin "1") (pinfunction "1_1") (pintype "passive"))
      (node (ref "R3AMP1M2") (pin "1") (pinfunction "1_1") (pintype "passive"))
      (node (ref "R3AMP1M3") (pin "1") (pinfunction "1_1") (pintype "passive"))
      (node (ref "R6AMP2M") (pin "1") (pinfunction "1_1") (pintype "passive"))
      (node (ref "R6AMP2M1") (pin "1") (pinfunction "1_1") (pintype "passive"))
      (node (ref "R6AMP2M2") (pin "1") (pinfunction "1_1") (pintype "passive"))
      (node (ref "R6AMP2M3") (pin "1") (pinfunction "1_1") (pintype "passive"))
    )
    (net (code "73") (name "unconnected-(R1-Pad2)") (class "Default")
      (node (ref "R1") (pin "2") (pinfunction "2_2") (pintype "passive"))
    )
    (net (code "74") (name "unconnected-(R2-Pad2)") (class "Default")
      (node (ref "R2") (pin "2") (pinfunction "2_2") (pintype "passive"))
    )
    (net (code "75") (name "unconnected-(R3-Pad2)") (class "Default")
      (node (ref "R3") (pin "2") (pinfunction "2_2") (pintype "passive"))
    )
    (net (code "76") (name "unconnected-(R9-Pad2)") (class "Default")
      (node (ref "R9") (pin "2") (pinfunction "2_2") (pintype "passive"))
    )
    (net (code "77") (name "unconnected-(U$1-NC-Pad6)") (class "Default")
      (node (ref "U$1") (pin "6") (pinfunction "NC_6") (pintype "no_connect"))
    )
    (net (code "78") (name "unconnected-(U$1-NC_2-Pad5)") (class "Default")
      (node (ref "U$1") (pin "5") (pinfunction "NC_2_5") (pintype "no_connect"))
    )
  )
)
